# PDTSetup_with_3535.net
KiCad netlist of a schematic drawn in EAGLE
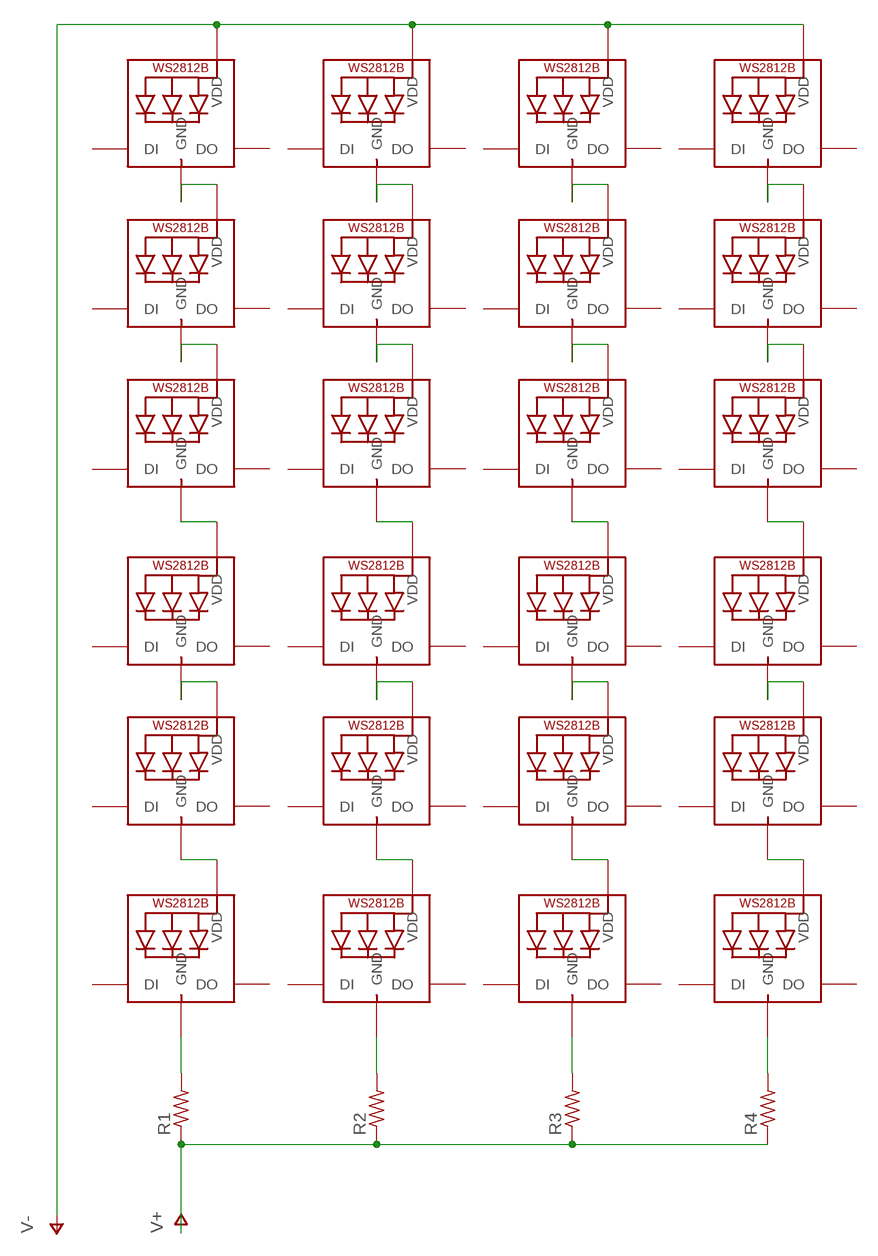
[diagram p0: schematic, sheet 1]

(export (version "E")
  (design (tool "Eeschema 10.0.6"))
  (components
    (comp (ref "LED1")
      (value "WS2812B3535")
      (footprint "eagle-import:LED3535")
      (libsource (lib "eagle-import") (part "WS2812B3535"))
    )
    (comp (ref "LED2")
      (value "WS2812B3535")
      (footprint "eagle-import:LED3535")
      (libsource (lib "eagle-import") (part "WS2812B3535"))
    )
    (comp (ref "LED3")
      (value "WS2812B3535")
      (footprint "eagle-import:LED3535")
      (libsource (lib "eagle-import") (part "WS2812B3535"))
    )
    (comp (ref "LED4")
      (value "WS2812B3535")
      (footprint "eagle-import:LED3535")
      (libsource (lib "eagle-import") (part "WS2812B3535"))
    )
    (comp (ref "LED5")
      (value "WS2812B3535")
      (footprint "eagle-import:LED3535")
      (libsource (lib "eagle-import") (part "WS2812B3535"))
    )
    (comp (ref "LED6")
      (value "WS2812B3535")
      (footprint "eagle-import:LED3535")
      (libsource (lib "eagle-import") (part "WS2812B3535"))
    )
    (comp (ref "LED7")
      (value "WS2812B3535")
      (footprint "eagle-import:LED3535")
      (libsource (lib "eagle-import") (part "WS2812B3535"))
    )
    (comp (ref "LED8")
      (value "WS2812B3535")
      (footprint "eagle-import:LED3535")
      (libsource (lib "eagle-import") (part "WS2812B3535"))
    )
    (comp (ref "LED9")
      (value "WS2812B3535")
      (footprint "eagle-import:LED3535")
      (libsource (lib "eagle-import") (part "WS2812B3535"))
    )
    (comp (ref "LED10")
      (value "WS2812B3535")
      (footprint "eagle-import:LED3535")
      (libsource (lib "eagle-import") (part "WS2812B3535"))
    )
    (comp (ref "LED11")
      (value "WS2812B3535")
      (footprint "eagle-import:LED3535")
      (libsource (lib "eagle-import") (part "WS2812B3535"))
    )
    (comp (ref "LED12")
      (value "WS2812B3535")
      (footprint "eagle-import:LED3535")
      (libsource (lib "eagle-import") (part "WS2812B3535"))
    )
    (comp (ref "LED13")
      (value "WS2812B3535")
      (footprint "eagle-import:LED3535")
      (libsource (lib "eagle-import") (part "WS2812B3535"))
    )
    (comp (ref "LED14")
      (value "WS2812B3535")
      (footprint "eagle-import:LED3535")
      (libsource (lib "eagle-import") (part "WS2812B3535"))
    )
    (comp (ref "LED15")
      (value "WS2812B3535")
      (footprint "eagle-import:LED3535")
      (libsource (lib "eagle-import") (part "WS2812B3535"))
    )
    (comp (ref "LED16")
      (value "WS2812B3535")
      (footprint "eagle-import:LED3535")
      (libsource (lib "eagle-import") (part "WS2812B3535"))
    )
    (comp (ref "LED17")
      (value "WS2812B3535")
      (footprint "eagle-import:LED3535")
      (libsource (lib "eagle-import") (part "WS2812B3535"))
    )
    (comp (ref "LED18")
      (value "WS2812B3535")
      (footprint "eagle-import:LED3535")
      (libsource (lib "eagle-import") (part "WS2812B3535"))
    )
    (comp (ref "LED19")
      (value "WS2812B3535")
      (footprint "eagle-import:LED3535")
      (libsource (lib "eagle-import") (part "WS2812B3535"))
    )
    (comp (ref "LED20")
      (value "WS2812B3535")
      (footprint "eagle-import:LED3535")
      (libsource (lib "eagle-import") (part "WS2812B3535"))
    )
    (comp (ref "LED21")
      (value "WS2812B3535")
      (footprint "eagle-import:LED3535")
      (libsource (lib "eagle-import") (part "WS2812B3535"))
    )
    (comp (ref "LED22")
      (value "WS2812B3535")
      (footprint "eagle-import:LED3535")
      (libsource (lib "eagle-import") (part "WS2812B3535"))
    )
    (comp (ref "LED23")
      (value "WS2812B3535")
      (footprint "eagle-import:LED3535")
      (libsource (lib "eagle-import") (part "WS2812B3535"))
    )
    (comp (ref "LED24")
      (value "WS2812B3535")
      (footprint "eagle-import:LED3535")
      (libsource (lib "eagle-import") (part "WS2812B3535"))
    )
    (comp (ref "R1")
      (value "R-US_0207/15")
      (footprint "eagle-import:0207_15")
      (libsource (lib "eagle-import") (part "R-US_0207/15"))
    )
    (comp (ref "R2")
      (value "R-US_0207/15")
      (footprint "eagle-import:0207_15")
      (libsource (lib "eagle-import") (part "R-US_0207/15"))
    )
    (comp (ref "R3")
      (value "R-US_0207/15")
      (footprint "eagle-import:0207_15")
      (libsource (lib "eagle-import") (part "R-US_0207/15"))
    )
    (comp (ref "R4")
      (value "R-US_0207/15")
      (footprint "eagle-import:0207_15")
      (libsource (lib "eagle-import") (part "R-US_0207/15"))
    )
  )
  (nets
    (net (code "1") (name "Net-(LED1-GND)") (class "Default")
      (node (ref "LED1") (pin "4") (pinfunction "GND_4") (pintype "power_in"))
      (node (ref "LED2") (pin "2") (pinfunction "VDD_2") (pintype "power_in"))
    )
    (net (code "2") (name "Net-(LED2-GND)") (class "Default")
      (node (ref "LED2") (pin "4") (pinfunction "GND_4") (pintype "power_in"))
      (node (ref "LED3") (pin "2") (pinfunction "VDD_2") (pintype "power_in"))
    )
    (net (code "3") (name "Net-(LED3-GND)") (class "Default")
      (node (ref "LED3") (pin "4") (pinfunction "GND_4") (pintype "power_in"))
      (node (ref "LED4") (pin "2") (pinfunction "VDD_2") (pintype "power_in"))
    )
    (net (code "4") (name "Net-(LED4-GND)") (class "Default")
      (node (ref "LED4") (pin "4") (pinfunction "GND_4") (pintype "power_in"))
      (node (ref "LED5") (pin "2") (pinfunction "VDD_2") (pintype "power_in"))
    )
    (net (code "5") (name "Net-(LED5-GND)") (class "Default")
      (node (ref "LED5") (pin "4") (pinfunction "GND_4") (pintype "power_in"))
      (node (ref "LED6") (pin "2") (pinfunction "VDD_2") (pintype "power_in"))
    )
    (net (code "6") (name "Net-(LED6-GND)") (class "Default")
      (node (ref "LED6") (pin "4") (pinfunction "GND_4") (pintype "power_in"))
      (node (ref "R1") (pin "2") (pinfunction "2_2") (pintype "passive"))
    )
    (net (code "7") (name "Net-(LED7-GND)") (class "Default")
      (node (ref "LED7") (pin "4") (pinfunction "GND_4") (pintype "power_in"))
      (node (ref "LED8") (pin "2") (pinfunction "VDD_2") (pintype "power_in"))
    )
    (net (code "8") (name "Net-(LED8-GND)") (class "Default")
      (node (ref "LED8") (pin "4") (pinfunction "GND_4") (pintype "power_in"))
      (node (ref "LED9") (pin "2") (pinfunction "VDD_2") (pintype "power_in"))
    )
    (net (code "9") (name "Net-(LED10-GND)") (class "Default")
      (node (ref "LED10") (pin "4") (pinfunction "GND_4") (pintype "power_in"))
      (node (ref "LED11") (pin "2") (pinfunction "VDD_2") (pintype "power_in"))
    )
    (net (code "10") (name "Net-(LED10-VDD)") (class "Default")
      (node (ref "LED10") (pin "2") (pinfunction "VDD_2") (pintype "power_in"))
      (node (ref "LED9") (pin "4") (pinfunction "GND_4") (pintype "power_in"))
    )
    (net (code "11") (name "Net-(LED11-GND)") (class "Default")
      (node (ref "LED11") (pin "4") (pinfunction "GND_4") (pintype "power_in"))
      (node (ref "LED12") (pin "2") (pinfunction "VDD_2") (pintype "power_in"))
    )
    (net (code "12") (name "Net-(LED12-GND)") (class "Default")
      (node (ref "LED12") (pin "4") (pinfunction "GND_4") (pintype "power_in"))
      (node (ref "R2") (pin "2") (pinfunction "2_2") (pintype "passive"))
    )
    (net (code "13") (name "Net-(LED13-GND)") (class "Default")
      (node (ref "LED13") (pin "4") (pinfunction "GND_4") (pintype "power_in"))
      (node (ref "R3") (pin "2") (pinfunction "2_2") (pintype "passive"))
    )
    (net (code "14") (name "Net-(LED13-VDD)") (class "Default")
      (node (ref "LED13") (pin "2") (pinfunction "VDD_2") (pintype "power_in"))
      (node (ref "LED14") (pin "4") (pinfunction "GND_4") (pintype "power_in"))
    )
    (net (code "15") (name "Net-(LED14-VDD)") (class "Default")
      (node (ref "LED14") (pin "2") (pinfunction "VDD_2") (pintype "power_in"))
      (node (ref "LED15") (pin "4") (pinfunction "GND_4") (pintype "power_in"))
    )
    (net (code "16") (name "Net-(LED15-VDD)") (class "Default")
      (node (ref "LED15") (pin "2") (pinfunction "VDD_2") (pintype "power_in"))
      (node (ref "LED16") (pin "4") (pinfunction "GND_4") (pintype "power_in"))
    )
    (net (code "17") (name "Net-(LED16-VDD)") (class "Default")
      (node (ref "LED16") (pin "2") (pinfunction "VDD_2") (pintype "power_in"))
      (node (ref "LED17") (pin "4") (pinfunction "GND_4") (pintype "power_in"))
    )
    (net (code "18") (name "Net-(LED17-VDD)") (class "Default")
      (node (ref "LED17") (pin "2") (pinfunction "VDD_2") (pintype "power_in"))
      (node (ref "LED18") (pin "4") (pinfunction "GND_4") (pintype "power_in"))
    )
    (net (code "19") (name "Net-(LED19-GND)") (class "Default")
      (node (ref "LED19") (pin "4") (pinfunction "GND_4") (pintype "power_in"))
      (node (ref "LED20") (pin "2") (pinfunction "VDD_2") (pintype "power_in"))
    )
    (net (code "20") (name "Net-(LED20-GND)") (class "Default")
      (node (ref "LED20") (pin "4") (pinfunction "GND_4") (pintype "power_in"))
      (node (ref "LED21") (pin "2") (pinfunction "VDD_2") (pintype "power_in"))
    )
    (net (code "21") (name "Net-(LED21-GND)") (class "Default")
      (node (ref "LED21") (pin "4") (pinfunction "GND_4") (pintype "power_in"))
      (node (ref "LED22") (pin "2") (pinfunction "VDD_2") (pintype "power_in"))
    )
    (net (code "22") (name "Net-(LED22-GND)") (class "Default")
      (node (ref "LED22") (pin "4") (pinfunction "GND_4") (pintype "power_in"))
      (node (ref "LED23") (pin "2") (pinfunction "VDD_2") (pintype "power_in"))
    )
    (net (code "23") (name "Net-(LED23-GND)") (class "Default")
      (node (ref "LED23") (pin "4") (pinfunction "GND_4") (pintype "power_in"))
      (node (ref "LED24") (pin "2") (pinfunction "VDD_2") (pintype "power_in"))
    )
    (net (code "24") (name "Net-(LED24-GND)") (class "Default")
      (node (ref "LED24") (pin "4") (pinfunction "GND_4") (pintype "power_in"))
      (node (ref "R4") (pin "2") (pinfunction "2_2") (pintype "passive"))
    )
    (net (code "25") (name "V+") (class "Default")
      (node (ref "R1") (pin "1") (pinfunction "1_1") (pintype "passive"))
      (node (ref "R2") (pin "1") (pinfunction "1_1") (pintype "passive"))
      (node (ref "R3") (pin "1") (pinfunction "1_1") (pintype "passive"))
      (node (ref "R4") (pin "1") (pinfunction "1_1") (pintype "passive"))
    )
    (net (code "26") (name "V-") (class "Default")
      (node (ref "LED1") (pin "2") (pinfunction "VDD_2") (pintype "power_in"))
      (node (ref "LED18") (pin "2") (pinfunction "VDD_2") (pintype "power_in"))
      (node (ref "LED19") (pin "2") (pinfunction "VDD_2") (pintype "power_in"))
      (node (ref "LED7") (pin "2") (pinfunction "VDD_2") (pintype "power_in"))
    )
    (net (code "27") (name "unconnected-(LED1-DI-Pad1)") (class "Default")
      (node (ref "LED1") (pin "1") (pinfunction "DI_1") (pintype "input"))
    )
    (net (code "28") (name "unconnected-(LED1-DO-Pad3)") (class "Default")
      (node (ref "LED1") (pin "3") (pinfunction "DO_3") (pintype "output"))
    )
    (net (code "29") (name "unconnected-(LED2-DI-Pad1)") (class "Default")
      (node (ref "LED2") (pin "1") (pinfunction "DI_1") (pintype "input"))
    )
    (net (code "30") (name "unconnected-(LED2-DO-Pad3)") (class "Default")
      (node (ref "LED2") (pin "3") (pinfunction "DO_3") (pintype "output"))
    )
    (net (code "31") (name "unconnected-(LED3-DI-Pad1)") (class "Default")
      (node (ref "LED3") (pin "1") (pinfunction "DI_1") (pintype "input"))
    )
    (net (code "32") (name "unconnected-(LED3-DO-Pad3)") (class "Default")
      (node (ref "LED3") (pin "3") (pinfunction "DO_3") (pintype "output"))
    )
    (net (code "33") (name "unconnected-(LED4-DI-Pad1)") (class "Default")
      (node (ref "LED4") (pin "1") (pinfunction "DI_1") (pintype "input"))
    )
    (net (code "34") (name "unconnected-(LED4-DO-Pad3)") (class "Default")
      (node (ref "LED4") (pin "3") (pinfunction "DO_3") (pintype "output"))
    )
    (net (code "35") (name "unconnected-(LED5-DI-Pad1)") (class "Default")
      (node (ref "LED5") (pin "1") (pinfunction "DI_1") (pintype "input"))
    )
    (net (code "36") (name "unconnected-(LED5-DO-Pad3)") (class "Default")
      (node (ref "LED5") (pin "3") (pinfunction "DO_3") (pintype "output"))
    )
    (net (code "37") (name "unconnected-(LED6-DI-Pad1)") (class "Default")
      (node (ref "LED6") (pin "1") (pinfunction "DI_1") (pintype "input"))
    )
    (net (code "38") (name "unconnected-(LED6-DO-Pad3)") (class "Default")
      (node (ref "LED6") (pin "3") (pinfunction "DO_3") (pintype "output"))
    )
    (net (code "39") (name "unconnected-(LED7-DI-Pad1)") (class "Default")
      (node (ref "LED7") (pin "1") (pinfunction "DI_1") (pintype "input"))
    )
    (net (code "40") (name "unconnected-(LED7-DO-Pad3)") (class "Default")
      (node (ref "LED7") (pin "3") (pinfunction "DO_3") (pintype "output"))
    )
    (net (code "41") (name "unconnected-(LED8-DI-Pad1)") (class "Default")
      (node (ref "LED8") (pin "1") (pinfunction "DI_1") (pintype "input"))
    )
    (net (code "42") (name "unconnected-(LED8-DO-Pad3)") (class "Default")
      (node (ref "LED8") (pin "3") (pinfunction "DO_3") (pintype "output"))
    )
    (net (code "43") (name "unconnected-(LED9-DI-Pad1)") (class "Default")
      (node (ref "LED9") (pin "1") (pinfunction "DI_1") (pintype "input"))
    )
    (net (code "44") (name "unconnected-(LED9-DO-Pad3)") (class "Default")
      (node (ref "LED9") (pin "3") (pinfunction "DO_3") (pintype "output"))
    )
    (net (code "45") (name "unconnected-(LED10-DI-Pad1)") (class "Default")
      (node (ref "LED10") (pin "1") (pinfunction "DI_1") (pintype "input"))
    )
    (net (code "46") (name "unconnected-(LED10-DO-Pad3)") (class "Default")
      (node (ref "LED10") (pin "3") (pinfunction "DO_3") (pintype "output"))
    )
    (net (code "47") (name "unconnected-(LED11-DI-Pad1)") (class "Default")
      (node (ref "LED11") (pin "1") (pinfunction "DI_1") (pintype "input"))
    )
    (net (code "48") (name "unconnected-(LED11-DO-Pad3)") (class "Default")
      (node (ref "LED11") (pin "3") (pinfunction "DO_3") (pintype "output"))
    )
    (net (code "49") (name "unconnected-(LED12-DI-Pad1)") (class "Default")
      (node (ref "LED12") (pin "1") (pinfunction "DI_1") (pintype "input"))
    )
    (net (code "50") (name "unconnected-(LED12-DO-Pad3)") (class "Default")
      (node (ref "LED12") (pin "3") (pinfunction "DO_3") (pintype "output"))
    )
    (net (code "51") (name "unconnected-(LED13-DI-Pad1)") (class "Default")
      (node (ref "LED13") (pin "1") (pinfunction "DI_1") (pintype "input"))
    )
    (net (code "52") (name "unconnected-(LED13-DO-Pad3)") (class "Default")
      (node (ref "LED13") (pin "3") (pinfunction "DO_3") (pintype "output"))
    )
    (net (code "53") (name "unconnected-(LED14-DI-Pad1)") (class "Default")
      (node (ref "LED14") (pin "1") (pinfunction "DI_1") (pintype "input"))
    )
    (net (code "54") (name "unconnected-(LED14-DO-Pad3)") (class "Default")
      (node (ref "LED14") (pin "3") (pinfunction "DO_3") (pintype "output"))
    )
    (net (code "55") (name "unconnected-(LED15-DI-Pad1)") (class "Default")
      (node (ref "LED15") (pin "1") (pinfunction "DI_1") (pintype "input"))
    )
    (net (code "56") (name "unconnected-(LED15-DO-Pad3)") (class "Default")
      (node (ref "LED15") (pin "3") (pinfunction "DO_3") (pintype "output"))
    )
    (net (code "57") (name "unconnected-(LED16-DI-Pad1)") (class "Default")
      (node (ref "LED16") (pin "1") (pinfunction "DI_1") (pintype "input"))
    )
    (net (code "58") (name "unconnected-(LED16-DO-Pad3)") (class "Default")
      (node (ref "LED16") (pin "3") (pinfunction "DO_3") (pintype "output"))
    )
    (net (code "59") (name "unconnected-(LED17-DI-Pad1)") (class "Default")
      (node (ref "LED17") (pin "1") (pinfunction "DI_1") (pintype "input"))
    )
    (net (code "60") (name "unconnected-(LED17-DO-Pad3)") (class "Default")
      (node (ref "LED17") (pin "3") (pinfunction "DO_3") (pintype "output"))
    )
    (net (code "61") (name "unconnected-(LED18-DI-Pad1)") (class "Default")
      (node (ref "LED18") (pin "1") (pinfunction "DI_1") (pintype "input"))
    )
    (net (code "62") (name "unconnected-(LED18-DO-Pad3)") (class "Default")
      (node (ref "LED18") (pin "3") (pinfunction "DO_3") (pintype "output"))
    )
    (net (code "63") (name "unconnected-(LED19-DI-Pad1)") (class "Default")
      (node (ref "LED19") (pin "1") (pinfunction "DI_1") (pintype "input"))
    )
    (net (code "64") (name "unconnected-(LED19-DO-Pad3)") (class "Default")
      (node (ref "LED19") (pin "3") (pinfunction "DO_3") (pintype "output"))
    )
    (net (code "65") (name "unconnected-(LED20-DI-Pad1)") (class "Default")
      (node (ref "LED20") (pin "1") (pinfunction "DI_1") (pintype "input"))
    )
    (net (code "66") (name "unconnected-(LED20-DO-Pad3)") (class "Default")
      (node (ref "LED20") (pin "3") (pinfunction "DO_3") (pintype "output"))
    )
    (net (code "67") (name "unconnected-(LED21-DI-Pad1)") (class "Default")
      (node (ref "LED21") (pin "1") (pinfunction "DI_1") (pintype "input"))
    )
    (net (code "68") (name "unconnected-(LED21-DO-Pad3)") (class "Default")
      (node (ref "LED21") (pin "3") (pinfunction "DO_3") (pintype "output"))
    )
    (net (code "69") (name "unconnected-(LED22-DI-Pad1)") (class "Default")
      (node (ref "LED22") (pin "1") (pinfunction "DI_1") (pintype "input"))
    )
    (net (code "70") (name "unconnected-(LED22-DO-Pad3)") (class "Default")
      (node (ref "LED22") (pin "3") (pinfunction "DO_3") (pintype "output"))
    )
    (net (code "71") (name "unconnected-(LED23-DI-Pad1)") (class "Default")
      (node (ref "LED23") (pin "1") (pinfunction "DI_1") (pintype "input"))
    )
    (net (code "72") (name "unconnected-(LED23-DO-Pad3)") (class "Default")
      (node (ref "LED23") (pin "3") (pinfunction "DO_3") (pintype "output"))
    )
    (net (code "73") (name "unconnected-(LED24-DI-Pad1)") (class "Default")
      (node (ref "LED24") (pin "1") (pinfunction "DI_1") (pintype "input"))
    )
    (net (code "74") (name "unconnected-(LED24-DO-Pad3)") (class "Default")
      (node (ref "LED24") (pin "3") (pinfunction "DO_3") (pintype "output"))
    )
  )
)
